# touch_control.net
KiCad netlist of a schematic drawn in Altium Designer
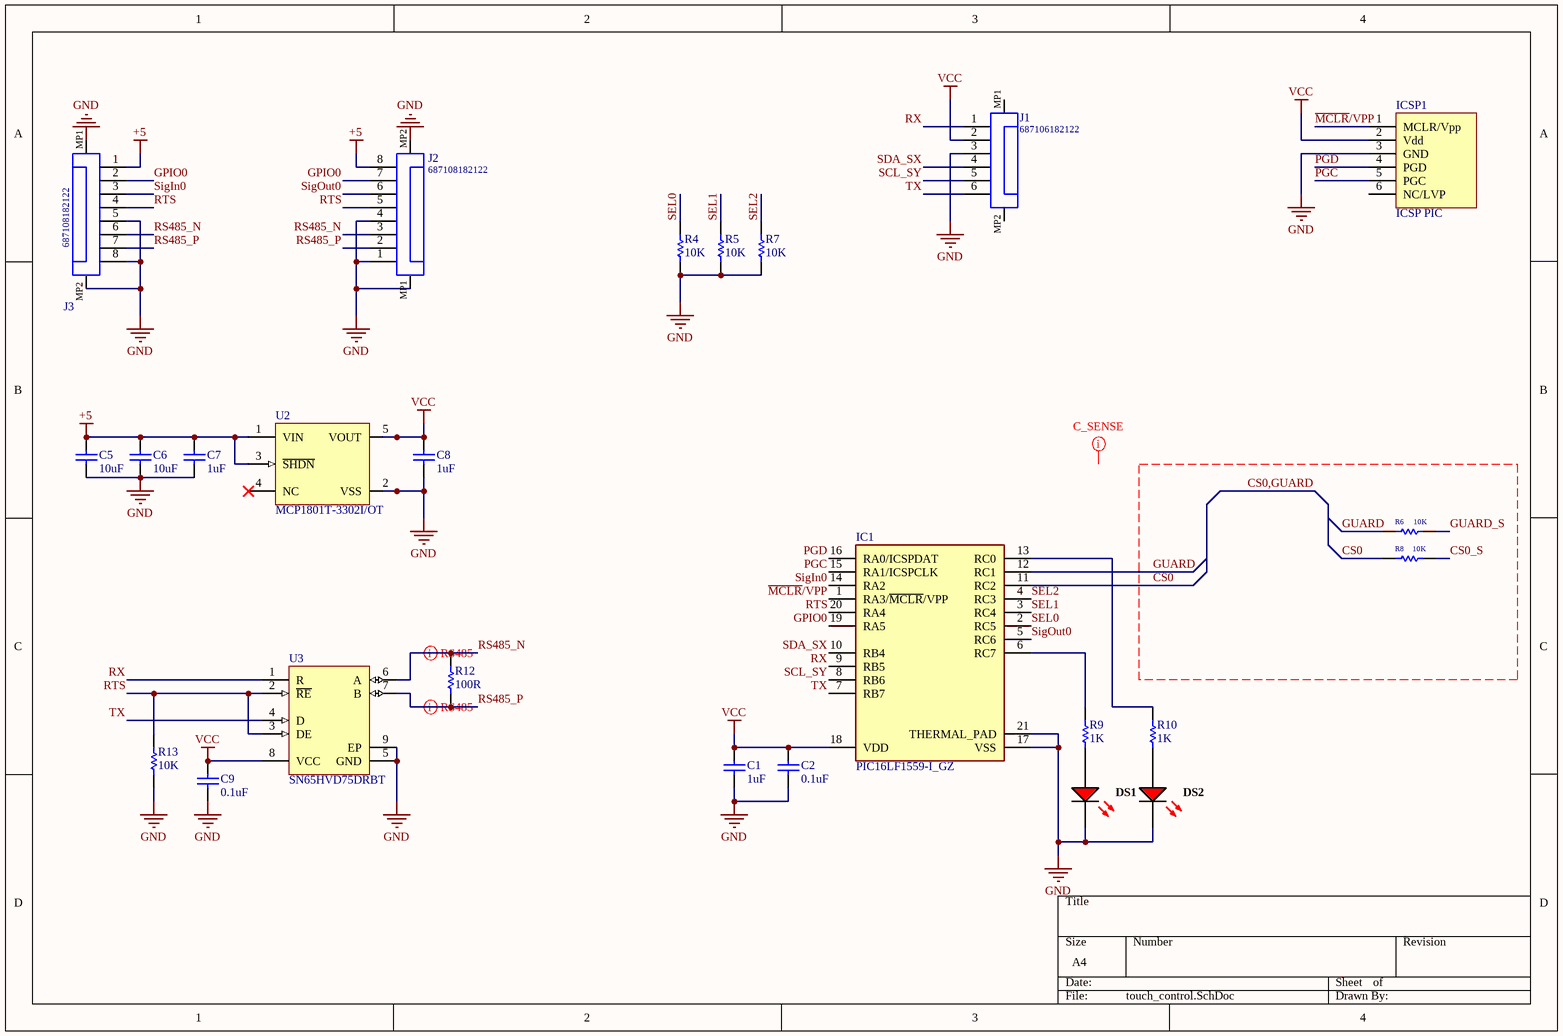
[diagram p0: touch_control.SchDoc]

(export (version "E")
  (design (tool "Eeschema 10.0.6"))
  (components
    (comp (ref "C1")
      (value "1uF")
      (footprint "CAPC1608X95X40NL15T15")
      (fields (field (name "MANUFACTURER") "Vitramon") (field (name "PART NUMBER") "VJ0603G105KXYCW1BC"))
      (libsource (lib "Altium Content Vault") (part "CAP"))
    )
    (comp (ref "C2")
      (value "0.1uF")
      (footprint "CAPC1608X95X40NL15T15")
      (fields (field (name "PART NUMBER") "VJ0603Y104JXQCW1BC") (field (name "MANUFACTURER") "Vitramon"))
      (libsource (lib "Altium Content Vault") (part "CAP"))
    )
    (comp (ref "C5")
      (value "10uF")
      (footprint "CAPC1608X90X35NL10T15")
      (fields (field (name "PART NUMBER") "GRM188R60J106ME47D") (field (name "MANUFACTURER") "Murata"))
      (libsource (lib "Altium Content Vault") (part "CAP"))
    )
    (comp (ref "C6")
      (value "10uF")
      (footprint "CAPC1608X90X35NL10T15")
      (fields (field (name "PART NUMBER") "GRM188R60J106ME47D") (field (name "MANUFACTURER") "Murata"))
      (libsource (lib "Altium Content Vault") (part "CAP"))
    )
    (comp (ref "C7")
      (value "1uF")
      (footprint "CAPC1608X95X40NL15T15")
      (fields (field (name "MANUFACTURER") "Vitramon") (field (name "PART NUMBER") "VJ0603G105KXYCW1BC"))
      (libsource (lib "Altium Content Vault") (part "CAP"))
    )
    (comp (ref "C8")
      (value "1uF")
      (footprint "CAPC1608X95X40NL15T15")
      (fields (field (name "MANUFACTURER") "Vitramon") (field (name "PART NUMBER") "VJ0603G105KXYCW1BC"))
      (libsource (lib "Altium Content Vault") (part "CAP"))
    )
    (comp (ref "C9")
      (value "0.1uF")
      (footprint "CAPC1608X95X40NL15T15")
      (fields (field (name "PART NUMBER") "VJ0603Y104JXQCW1BC") (field (name "MANUFACTURER") "Vitramon"))
      (libsource (lib "Altium Content Vault") (part "CAP"))
    )
    (comp (ref "DS1")
      (value "APG1608SURKC/T")
      (footprint "KING-LED0603-25-RED_V")
      (fields (field (name "MANUFACTURER") "Kingbright"))
      (libsource (lib "Altium Content Vault") (part "KING-LED_RED_A1K2-2"))
    )
    (comp (ref "DS2")
      (value "APG1608SURKC/T")
      (footprint "KING-LED0603-25-RED_V")
      (fields (field (name "MANUFACTURER") "Kingbright"))
      (libsource (lib "Altium Content Vault") (part "KING-LED_RED_A1K2-2"))
    )
    (comp (ref "IC1")
      (value "PIC16LF1559-I_GZ")
      (footprint "SamacSys:QFN50P400X400X55-21N-D")
      (description "Integrated Circuit")
      (fields
        (field (name "MANUFACTURER_PART_NUMBER") "PIC16LF1559-I/GZ")
        (field (name "MOUSER PART NUMBER") "579-PIC16LF1559-I/GZ")
      )
      (libsource (lib "SamacSys") (part "PIC16LF1559-I_GZ"))
    )
    (comp (ref "ICSP1")
      (value "ICSP PIC")
      (footprint "TC2030-MCP")
      (libsource (lib "TC2030") (part "ICSP PIC"))
    )
    (comp (ref "J1")
      (value "687106182122")
      (footprint "687106182122")
      (description "SMT ZIF Connectors WR-FPC, Horizontal, Back Locking Dual Contact, pitch 0.5 mm, 6 pins")
      (fields (field (name "MANUFACTURER") "Wurth Elektronik") (field (name "PUBLISHER") "WurthElektronik"))
      (libsource (lib "Altium Content Vault") (part "WE-68X1061XXX22-6"))
    )
    (comp (ref "J2")
      (value "687108182122")
      (footprint "687108182122")
      (description "SMT ZIF Connectors WR-FPC, Horizontal, Back Locking Dual Contact, pitch 0.5 mm, 8 pins")
      (fields (field (name "MANUFACTURER") "Wurth Elektronik") (field (name "PUBLISHER") "WurthElektronik"))
      (libsource (lib "Altium Content Vault") (part "WE-68X1081XXX22-8"))
    )
    (comp (ref "J3")
      (value "687108182122")
      (footprint "687108182122")
      (description "SMT ZIF Connectors WR-FPC, Horizontal, Back Locking Dual Contact, pitch 0.5 mm, 8 pins")
      (fields (field (name "MANUFACTURER") "Wurth Elektronik") (field (name "PUBLISHER") "WurthElektronik"))
      (libsource (lib "Altium Content Vault") (part "WE-68X1081XXX22-8"))
    )
    (comp (ref "R4")
      (value "10K")
      (footprint "RESC0603(1608)_N")
      (description "10K 0.1W 1% 0603 (1608 Metric)  SMD")
      (fields (field (name "POWER") "0.1 W") (field (name "TOLERANCE") "1 %"))
      (libsource (lib "Altium Content Vault") (part "RES"))
    )
    (comp (ref "R5")
      (value "10K")
      (footprint "RESC0603(1608)_N")
      (description "10K 0.1W 1% 0603 (1608 Metric)  SMD")
      (fields (field (name "POWER") "0.1 W") (field (name "TOLERANCE") "1 %"))
      (libsource (lib "Altium Content Vault") (part "RES"))
    )
    (comp (ref "R6")
      (value "10K")
      (footprint "RESC0603(1608)_N")
      (description "10K 0.1W 1% 0603 (1608 Metric)  SMD")
      (fields (field (name "POWER") "0.1 W") (field (name "TOLERANCE") "1 %"))
      (libsource (lib "Altium Content Vault") (part "RES"))
    )
    (comp (ref "R7")
      (value "10K")
      (footprint "RESC0603(1608)_N")
      (description "10K 0.1W 1% 0603 (1608 Metric)  SMD")
      (fields (field (name "POWER") "0.1 W") (field (name "TOLERANCE") "1 %"))
      (libsource (lib "Altium Content Vault") (part "RES"))
    )
    (comp (ref "R8")
      (value "10K")
      (footprint "RESC0603(1608)_N")
      (description "10K 0.1W 1% 0603 (1608 Metric)  SMD")
      (fields (field (name "POWER") "0.1 W") (field (name "TOLERANCE") "1 %"))
      (libsource (lib "Altium Content Vault") (part "RES"))
    )
    (comp (ref "R9")
      (value "1K")
      (footprint "RESC0603(1608)_N")
      (description "10K 0.1W 1% 0603 (1608 Metric)  SMD")
      (fields (field (name "POWER") "0.1 W") (field (name "TOLERANCE") "1 %"))
      (libsource (lib "Altium Content Vault") (part "RES"))
    )
    (comp (ref "R10")
      (value "1K")
      (footprint "RESC0603(1608)_N")
      (description "10K 0.1W 1% 0603 (1608 Metric)  SMD")
      (fields (field (name "POWER") "0.1 W") (field (name "TOLERANCE") "1 %"))
      (libsource (lib "Altium Content Vault") (part "RES"))
    )
    (comp (ref "R12")
      (value "100R")
      (footprint "RESC0603(1608)_N")
      (description "10K 0.1W 1% 0603 (1608 Metric)  SMD")
      (fields (field (name "POWER") "0.1 W") (field (name "TOLERANCE") "1 %"))
      (libsource (lib "Altium Content Vault") (part "RES"))
    )
    (comp (ref "R13")
      (value "10K")
      (footprint "RESC0603(1608)_N")
      (description "10K 0.1W 1% 0603 (1608 Metric)  SMD")
      (fields (field (name "POWER") "0.1 W") (field (name "TOLERANCE") "1 %"))
      (libsource (lib "Altium Content Vault") (part "RES"))
    )
    (comp (ref "U2")
      (value "MCP1801T-3302I/OT")
      (footprint "SOT-23-OT5_M")
      (description "150 mA, High PSRR, Low Quiescent Current LDO, 5-Pin SOT-23, Industrial Temperature, Tape and Reel")
      (libsource (lib "Altium Content Vault") (part "PM-LINEREG-MCP1801-IL5"))
    )
    (comp (ref "U3")
      (value "SN65HVD75DRBT")
      (footprint "DRB0008B_V")
      (fields (field (name "MANUFACTURER") "Texas Instruments"))
      (libsource (lib "Altium Content Vault") (part "TI-SN65HVD7X-SON_DRB-8"))
    )
  )
  (nets
    (net (code "2") (name "+5") (class "Default")
      (node (ref "C5") (pin "2") (pinfunction "2_2") (pintype "passive"))
      (node (ref "C6") (pin "2") (pinfunction "2_2") (pintype "passive"))
      (node (ref "C7") (pin "2") (pinfunction "2_2") (pintype "passive"))
      (node (ref "J2") (pin "8") (pinfunction "8_8") (pintype "passive"))
      (node (ref "J3") (pin "1") (pinfunction "1_1") (pintype "passive"))
      (node (ref "U2") (pin "1") (pinfunction "VIN_1") (pintype "power_in"))
      (node (ref "U2") (pin "3") (pinfunction "~{SHDN}_3") (pintype "input"))
    )
    (net (code "3") (name "/CS0") (class "Default")
      (node (ref "IC1") (pin "11") (pinfunction "RC2_11") (pintype "passive"))
      (node (ref "R8") (pin "1") (pinfunction "1_1") (pintype "passive"))
    )
    (net (code "4") (name "/CS0_S") (class "Default")
      (node (ref "R8") (pin "2") (pinfunction "2_2") (pintype "passive"))
    )
    (net (code "5") (name "/GPIO0") (class "Default")
      (node (ref "IC1") (pin "19") (pinfunction "RA5_19") (pintype "passive"))
      (node (ref "J2") (pin "7") (pinfunction "7_7") (pintype "passive"))
      (node (ref "J3") (pin "2") (pinfunction "2_2") (pintype "passive"))
    )
    (net (code "6") (name "/GUARD") (class "Default")
      (node (ref "IC1") (pin "12") (pinfunction "RC1_12") (pintype "passive"))
      (node (ref "R6") (pin "1") (pinfunction "1_1") (pintype "passive"))
    )
    (net (code "7") (name "/GUARD_S") (class "Default")
      (node (ref "R6") (pin "2") (pinfunction "2_2") (pintype "passive"))
    )
    (net (code "8") (name "/PGC") (class "Default")
      (node (ref "IC1") (pin "15") (pinfunction "RA1/ICSPCLK_15") (pintype "passive"))
      (node (ref "ICSP1") (pin "5") (pinfunction "PGC_5") (pintype "passive"))
    )
    (net (code "9") (name "/PGD") (class "Default")
      (node (ref "IC1") (pin "16") (pinfunction "RA0/ICSPDAT_16") (pintype "passive"))
      (node (ref "ICSP1") (pin "4") (pinfunction "PGD_4") (pintype "passive"))
    )
    (net (code "10") (name "/RS485_N") (class "Default")
      (node (ref "J2") (pin "3") (pinfunction "3_3") (pintype "passive"))
      (node (ref "J3") (pin "6") (pinfunction "6_6") (pintype "passive"))
      (node (ref "R12") (pin "1") (pinfunction "1_1") (pintype "passive"))
      (node (ref "U3") (pin "6") (pinfunction "A_6") (pintype "bidirectional"))
    )
    (net (code "11") (name "/RS485_P") (class "Default")
      (node (ref "J2") (pin "2") (pinfunction "2_2") (pintype "passive"))
      (node (ref "J3") (pin "7") (pinfunction "7_7") (pintype "passive"))
      (node (ref "R12") (pin "2") (pinfunction "2_2") (pintype "passive"))
      (node (ref "U3") (pin "7") (pinfunction "B_7") (pintype "bidirectional"))
    )
    (net (code "12") (name "/RTS") (class "Default")
      (node (ref "IC1") (pin "20") (pinfunction "RA4_20") (pintype "passive"))
      (node (ref "J2") (pin "5") (pinfunction "5_5") (pintype "passive"))
      (node (ref "J3") (pin "4") (pinfunction "4_4") (pintype "passive"))
      (node (ref "R13") (pin "1") (pinfunction "1_1") (pintype "passive"))
      (node (ref "U3") (pin "2") (pinfunction "~{RE}_2") (pintype "input"))
      (node (ref "U3") (pin "3") (pinfunction "DE_3") (pintype "input"))
    )
    (net (code "13") (name "/RX") (class "Default")
      (node (ref "IC1") (pin "9") (pinfunction "RB5_9") (pintype "passive"))
      (node (ref "J1") (pin "1") (pinfunction "1_1") (pintype "passive"))
      (node (ref "U3") (pin "1") (pinfunction "R_1") (pintype "tri_state"))
    )
    (net (code "14") (name "/SCL_SY") (class "Default")
      (node (ref "IC1") (pin "8") (pinfunction "RB6_8") (pintype "passive"))
      (node (ref "J1") (pin "5") (pinfunction "5_5") (pintype "passive"))
    )
    (net (code "15") (name "/SDA_SX") (class "Default")
      (node (ref "IC1") (pin "10") (pinfunction "RB4_10") (pintype "passive"))
      (node (ref "J1") (pin "4") (pinfunction "4_4") (pintype "passive"))
    )
    (net (code "16") (name "/SEL0") (class "Default")
      (node (ref "IC1") (pin "2") (pinfunction "RC5_2") (pintype "passive"))
      (node (ref "R4") (pin "1") (pinfunction "1_1") (pintype "passive"))
    )
    (net (code "17") (name "/SEL1") (class "Default")
      (node (ref "IC1") (pin "3") (pinfunction "RC4_3") (pintype "passive"))
      (node (ref "R5") (pin "1") (pinfunction "1_1") (pintype "passive"))
    )
    (net (code "18") (name "/SEL2") (class "Default")
      (node (ref "IC1") (pin "4") (pinfunction "RC3_4") (pintype "passive"))
      (node (ref "R7") (pin "1") (pinfunction "1_1") (pintype "passive"))
    )
    (net (code "19") (name "/SigIn0") (class "Default")
      (node (ref "IC1") (pin "14") (pinfunction "RA2_14") (pintype "passive"))
      (node (ref "J3") (pin "3") (pinfunction "3_3") (pintype "passive"))
    )
    (net (code "20") (name "/SigOut0") (class "Default")
      (node (ref "IC1") (pin "5") (pinfunction "RC6_5") (pintype "passive"))
      (node (ref "J2") (pin "6") (pinfunction "6_6") (pintype "passive"))
    )
    (net (code "21") (name "/TX") (class "Default")
      (node (ref "IC1") (pin "7") (pinfunction "RB7_7") (pintype "passive"))
      (node (ref "J1") (pin "6") (pinfunction "6_6") (pintype "passive"))
      (node (ref "U3") (pin "4") (pinfunction "D_4") (pintype "input"))
    )
    (net (code "23") (name "/~{MCLR}{slash}VPP") (class "Default")
      (node (ref "IC1") (pin "1") (pinfunction "RA3/~{MCLR}/VPP_1") (pintype "passive"))
      (node (ref "ICSP1") (pin "1") (pinfunction "MCLR/Vpp_1") (pintype "passive"))
    )
    (net (code "24") (name "GND") (class "Default")
      (node (ref "C1") (pin "1") (pinfunction "1_1") (pintype "passive"))
      (node (ref "C2") (pin "1") (pinfunction "1_1") (pintype "passive"))
      (node (ref "C5") (pin "1") (pinfunction "1_1") (pintype "passive"))
      (node (ref "C6") (pin "1") (pinfunction "1_1") (pintype "passive"))
      (node (ref "C7") (pin "1") (pinfunction "1_1") (pintype "passive"))
      (node (ref "C8") (pin "1") (pinfunction "1_1") (pintype "passive"))
      (node (ref "C9") (pin "1") (pinfunction "1_1") (pintype "passive"))
      (node (ref "DS1") (pin "2") (pinfunction "K_2") (pintype "passive"))
      (node (ref "DS2") (pin "2") (pinfunction "K_2") (pintype "passive"))
      (node (ref "IC1") (pin "17") (pinfunction "VSS_17") (pintype "passive"))
      (node (ref "IC1") (pin "21") (pinfunction "THERMAL_PAD_21") (pintype "passive"))
      (node (ref "ICSP1") (pin "3") (pinfunction "GND_3") (pintype "passive"))
      (node (ref "J1") (pin "3") (pinfunction "3_3") (pintype "passive"))
      (node (ref "J2") (pin "1") (pinfunction "1_1") (pintype "passive"))
      (node (ref "J2") (pin "4") (pinfunction "4_4") (pintype "passive"))
      (node (ref "J2") (pin "MP1") (pinfunction "MP1_MP1") (pintype "passive"))
      (node (ref "J2") (pin "MP2") (pinfunction "MP2_MP2") (pintype "passive"))
      (node (ref "J3") (pin "5") (pinfunction "5_5") (pintype "passive"))
      (node (ref "J3") (pin "8") (pinfunction "8_8") (pintype "passive"))
      (node (ref "J3") (pin "MP1") (pinfunction "MP1_MP1") (pintype "passive"))
      (node (ref "J3") (pin "MP2") (pinfunction "MP2_MP2") (pintype "passive"))
      (node (ref "R13") (pin "2") (pinfunction "2_2") (pintype "passive"))
      (node (ref "R4") (pin "2") (pinfunction "2_2") (pintype "passive"))
      (node (ref "R5") (pin "2") (pinfunction "2_2") (pintype "passive"))
      (node (ref "R7") (pin "2") (pinfunction "2_2") (pintype "passive"))
      (node (ref "U2") (pin "2") (pinfunction "VSS_2") (pintype "power_in"))
      (node (ref "U3") (pin "5") (pinfunction "GND_5") (pintype "power_in"))
      (node (ref "U3") (pin "9") (pinfunction "EP_9") (pintype "passive"))
    )
    (net (code "25") (name "Net-(DS1-A)") (class "Default")
      (node (ref "DS1") (pin "1") (pinfunction "A_1") (pintype "passive"))
      (node (ref "R9") (pin "2") (pinfunction "2_2") (pintype "passive"))
    )
    (net (code "26") (name "Net-(DS2-A)") (class "Default")
      (node (ref "DS2") (pin "1") (pinfunction "A_1") (pintype "passive"))
      (node (ref "R10") (pin "2") (pinfunction "2_2") (pintype "passive"))
    )
    (net (code "27") (name "Net-(IC1-RC0)") (class "Default")
      (node (ref "IC1") (pin "13") (pinfunction "RC0_13") (pintype "passive"))
      (node (ref "R10") (pin "1") (pinfunction "1_1") (pintype "passive"))
    )
    (net (code "28") (name "Net-(IC1-RC7)") (class "Default")
      (node (ref "IC1") (pin "6") (pinfunction "RC7_6") (pintype "passive"))
      (node (ref "R9") (pin "1") (pinfunction "1_1") (pintype "passive"))
    )
    (net (code "29") (name "VCC") (class "Default")
      (node (ref "C1") (pin "2") (pinfunction "2_2") (pintype "passive"))
      (node (ref "C2") (pin "2") (pinfunction "2_2") (pintype "passive"))
      (node (ref "C8") (pin "2") (pinfunction "2_2") (pintype "passive"))
      (node (ref "C9") (pin "2") (pinfunction "2_2") (pintype "passive"))
      (node (ref "IC1") (pin "18") (pinfunction "VDD_18") (pintype "passive"))
      (node (ref "ICSP1") (pin "2") (pinfunction "Vdd_2") (pintype "passive"))
      (node (ref "J1") (pin "2") (pinfunction "2_2") (pintype "passive"))
      (node (ref "U2") (pin "5") (pinfunction "VOUT_5") (pintype "power_in"))
      (node (ref "U3") (pin "8") (pinfunction "VCC_8") (pintype "power_in"))
    )
    (net (code "30") (name "unconnected-(ICSP1-NC{slash}LVP-Pad6)") (class "Default")
      (node (ref "ICSP1") (pin "6") (pinfunction "NC/LVP_6") (pintype "passive"))
    )
    (net (code "31") (name "unconnected-(J1-PadMP1)") (class "Default")
      (node (ref "J1") (pin "MP1") (pinfunction "MP1_MP1") (pintype "passive"))
    )
    (net (code "32") (name "unconnected-(J1-PadMP2)") (class "Default")
      (node (ref "J1") (pin "MP2") (pinfunction "MP2_MP2") (pintype "passive"))
    )
    (net (code "33") (name "unconnected-(U2-NC-Pad4)") (class "Default")
      (node (ref "U2") (pin "4") (pinfunction "NC_4") (pintype "passive+no_connect"))
    )
  )
)
